# Temperature_inputs.net
KiCad netlist of a schematic drawn in Altium Designer
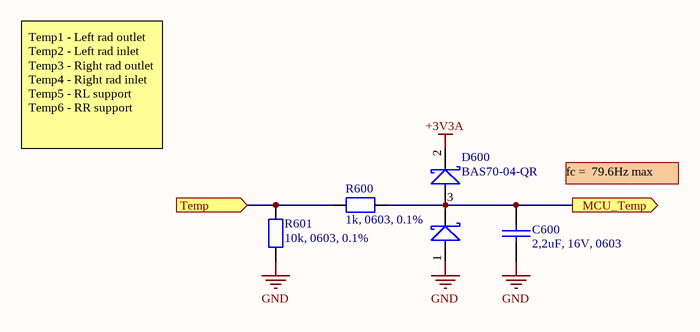
[diagram p0: Temperature_inputs.SchDoc]

(export (version "E")
  (design (tool "Eeschema 10.0.6"))
  (components
    (comp (ref "C600")
      (value "2,2uF, 16V, 0603")
      (footprint "CAP [0603] 1608")
      (description "Default capacitor part")
      (libsource (lib "Formula Student Team Tallinn (Estonia)") (part "Capacitor"))
    )
    (comp (ref "D600")
      (value "BAS70-04-QR")
      (footprint "SOT23-3")
      (description "Diode Small Signal Schottky 70V 70mA 3-Pin SOT-23 T/R")
      (fields (field (name "MANUFACTURER") "Nexperia"))
      (libsource (lib "Formula Student Team Tallinn (Estonia)") (part "Diode Rail-to-rail"))
    )
    (comp (ref "R600")
      (value "1k, 0603, 0.1%")
      (footprint "RES [0603] 1608")
      (description "Standard resistor part")
      (libsource (lib "Formula Student Team Tallinn (Estonia)") (part "Resistor"))
    )
    (comp (ref "R601")
      (value "10k, 0603, 0.1%")
      (footprint "RES [0603] 1608")
      (description "Standard resistor part")
      (libsource (lib "Formula Student Team Tallinn (Estonia)") (part "Resistor"))
    )
  )
  (nets
    (net (code "1") (name "+3V3A") (class "Default")
      (node (ref "D600") (pin "2") (pinfunction "2_2") (pintype "passive"))
    )
    (net (code "2") (name "/MCU_Temp") (class "Default")
      (node (ref "C600") (pin "1") (pinfunction "1_1") (pintype "passive"))
      (node (ref "D600") (pin "3") (pinfunction "3_3") (pintype "passive"))
      (node (ref "R600") (pin "1") (pinfunction "1_1") (pintype "passive"))
    )
    (net (code "3") (name "/Temp") (class "Default")
      (node (ref "R600") (pin "2") (pinfunction "2_2") (pintype "passive"))
      (node (ref "R601") (pin "1") (pinfunction "1_1") (pintype "passive"))
    )
    (net (code "4") (name "GND") (class "Default")
      (node (ref "C600") (pin "2") (pinfunction "2_2") (pintype "passive"))
      (node (ref "D600") (pin "1") (pinfunction "1_1") (pintype "passive"))
      (node (ref "R601") (pin "2") (pinfunction "2_2") (pintype "passive"))
    )
  )
)
